# Simon-COVID.net
KiCad netlist of a schematic drawn in EAGLE
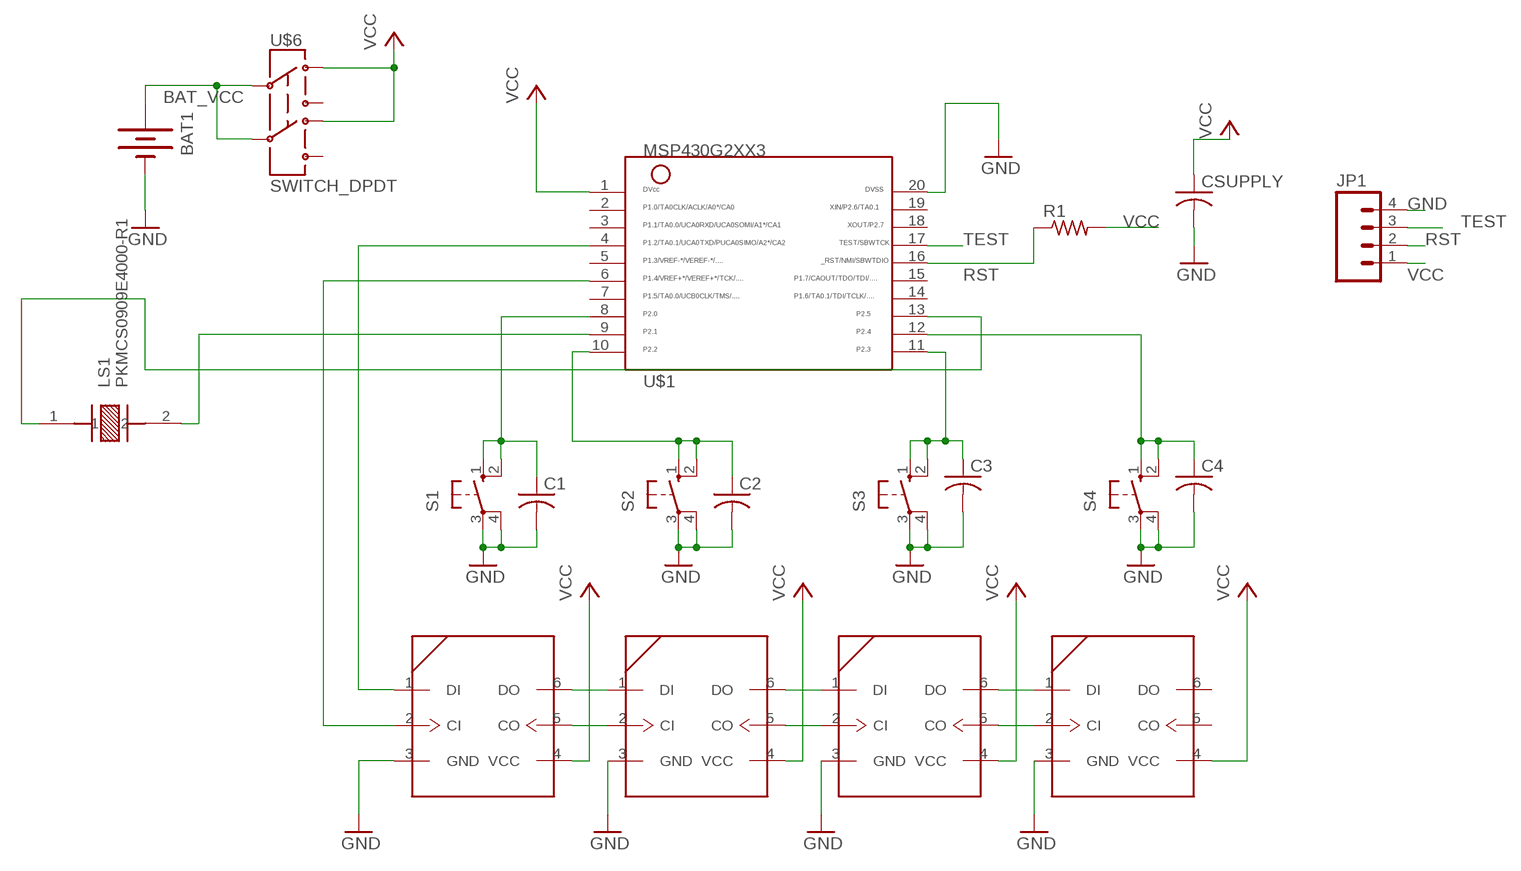
[diagram p0: schematic, sheet 1]

(export (version "E")
  (design (tool "Eeschema 10.0.6"))
  (components
    (comp (ref "BAT1")
      (value "BATTERY")
      (footprint "eagle-import:BATTERY_PACK_2AA")
      (libsource (lib "eagle-import") (part "BATTERY"))
    )
    (comp (ref "C1")
      (value "C-USC1206")
      (footprint "eagle-import:C1206")
      (libsource (lib "eagle-import") (part "C-USC1206"))
    )
    (comp (ref "C2")
      (value "C-USC1206")
      (footprint "eagle-import:C1206")
      (libsource (lib "eagle-import") (part "C-USC1206"))
    )
    (comp (ref "C3")
      (value "C-USC1206")
      (footprint "eagle-import:C1206")
      (libsource (lib "eagle-import") (part "C-USC1206"))
    )
    (comp (ref "C4")
      (value "C-USC1206")
      (footprint "eagle-import:C1206")
      (libsource (lib "eagle-import") (part "C-USC1206"))
    )
    (comp (ref "CSUPPLY")
      (value "C-USC1206")
      (footprint "eagle-import:C1206")
      (libsource (lib "eagle-import") (part "C-USC1206"))
    )
    (comp (ref "JP1")
      (value "M04LOCK")
      (footprint "eagle-import:1X04_LOCK")
      (libsource (lib "eagle-import") (part "M04LOCK"))
    )
    (comp (ref "LED1")
      (value "APA102")
      (footprint "eagle-import:5050")
      (libsource (lib "eagle-import") (part "APA102"))
    )
    (comp (ref "LED2")
      (value "APA102")
      (footprint "eagle-import:5050")
      (libsource (lib "eagle-import") (part "APA102"))
    )
    (comp (ref "LED3")
      (value "APA102")
      (footprint "eagle-import:5050")
      (libsource (lib "eagle-import") (part "APA102"))
    )
    (comp (ref "LED4")
      (value "APA102")
      (footprint "eagle-import:5050")
      (libsource (lib "eagle-import") (part "APA102"))
    )
    (comp (ref "LS1")
      (value "PKMCS0909E4000-R1")
      (footprint "eagle-import:XDCR_PKMCS0909E4000-R1")
      (fields (field (name "DIGI-KEY_PART_NUMBER") "490-9647-1-ND") (field (name "MF") "Murata"))
      (libsource (lib "eagle-import") (part "PKMCS0909E4000-R1"))
    )
    (comp (ref "R1")
      (value "R-US_R1206")
      (footprint "eagle-import:R1206")
      (libsource (lib "eagle-import") (part "R-US_R1206"))
    )
    (comp (ref "S1")
      (value "10-XX")
      (footprint "eagle-import:B3F-10XX")
      (fields (field (name "MPN") "B3F-1000"))
      (libsource (lib "eagle-import") (part "10-XX"))
    )
    (comp (ref "S2")
      (value "10-XX")
      (footprint "eagle-import:B3F-10XX")
      (fields (field (name "MPN") "B3F-1000"))
      (libsource (lib "eagle-import") (part "10-XX"))
    )
    (comp (ref "S3")
      (value "10-XX")
      (footprint "eagle-import:B3F-10XX")
      (fields (field (name "MPN") "B3F-1000"))
      (libsource (lib "eagle-import") (part "10-XX"))
    )
    (comp (ref "S4")
      (value "10-XX")
      (footprint "eagle-import:B3F-10XX")
      (fields (field (name "MPN") "B3F-1000"))
      (libsource (lib "eagle-import") (part "10-XX"))
    )
    (comp (ref "U$1")
      (value "MSP430G2XX3TSSOP")
      (footprint "eagle-import:PW20")
      (libsource (lib "eagle-import") (part "MSP430G2XX3TSSOP"))
    )
    (comp (ref "U$6")
      (value "SWITCH_DPDT")
      (footprint "eagle-import:JS_DPDT_TH")
      (libsource (lib "eagle-import") (part "SWITCH_DPDT"))
    )
  )
  (nets
    (net (code "1") (name "/BAT_VCC") (class "Default")
      (node (ref "BAT1") (pin "3V") (pinfunction "+_3V") (pintype "power_in"))
      (node (ref "U$6") (pin "2") (pinfunction "2_2") (pintype "bidirectional"))
      (node (ref "U$6") (pin "5") (pinfunction "5_5") (pintype "bidirectional"))
    )
    (net (code "2") (name "/RST") (class "Default")
      (node (ref "JP1") (pin "2") (pinfunction "2_2") (pintype "passive"))
      (node (ref "R1") (pin "1") (pinfunction "1_1") (pintype "passive"))
      (node (ref "U$1") (pin "16") (pinfunction "16_16") (pintype "bidirectional"))
    )
    (net (code "3") (name "/TEST") (class "Default")
      (node (ref "JP1") (pin "3") (pinfunction "3_3") (pintype "passive"))
      (node (ref "U$1") (pin "17") (pinfunction "17_17") (pintype "bidirectional"))
    )
    (net (code "4") (name "GND") (class "Default")
      (node (ref "BAT1") (pin "GND") (pinfunction "-_GND") (pintype "power_in"))
      (node (ref "C1") (pin "2") (pinfunction "2_2") (pintype "passive"))
      (node (ref "C2") (pin "2") (pinfunction "2_2") (pintype "passive"))
      (node (ref "C3") (pin "2") (pinfunction "2_2") (pintype "passive"))
      (node (ref "C4") (pin "2") (pinfunction "2_2") (pintype "passive"))
      (node (ref "CSUPPLY") (pin "2") (pinfunction "2_2") (pintype "passive"))
      (node (ref "JP1") (pin "4") (pinfunction "4_4") (pintype "passive"))
      (node (ref "LED1") (pin "3") (pinfunction "GND_3") (pintype "power_in"))
      (node (ref "LED2") (pin "3") (pinfunction "GND_3") (pintype "power_in"))
      (node (ref "LED3") (pin "3") (pinfunction "GND_3") (pintype "power_in"))
      (node (ref "LED4") (pin "3") (pinfunction "GND_3") (pintype "power_in"))
      (node (ref "S1") (pin "3") (pinfunction "P_3") (pintype "passive"))
      (node (ref "S1") (pin "4") (pinfunction "P1_4") (pintype "passive"))
      (node (ref "S2") (pin "3") (pinfunction "P_3") (pintype "passive"))
      (node (ref "S2") (pin "4") (pinfunction "P1_4") (pintype "passive"))
      (node (ref "S3") (pin "3") (pinfunction "P_3") (pintype "passive"))
      (node (ref "S3") (pin "4") (pinfunction "P1_4") (pintype "passive"))
      (node (ref "S4") (pin "3") (pinfunction "P_3") (pintype "passive"))
      (node (ref "S4") (pin "4") (pinfunction "P1_4") (pintype "passive"))
      (node (ref "U$1") (pin "20") (pinfunction "20_20") (pintype "bidirectional"))
    )
    (net (code "5") (name "Net-(LED1-CI)") (class "Default")
      (node (ref "LED1") (pin "2") (pinfunction "CI_2") (pintype "input"))
      (node (ref "U$1") (pin "6") (pinfunction "6_6") (pintype "bidirectional"))
    )
    (net (code "6") (name "Net-(LED1-CO)") (class "Default")
      (node (ref "LED1") (pin "5") (pinfunction "CO_5") (pintype "output"))
      (node (ref "LED2") (pin "2") (pinfunction "CI_2") (pintype "input"))
    )
    (net (code "7") (name "Net-(LED1-DI)") (class "Default")
      (node (ref "LED1") (pin "1") (pinfunction "DI_1") (pintype "input"))
      (node (ref "U$1") (pin "4") (pinfunction "4_4") (pintype "bidirectional"))
    )
    (net (code "8") (name "Net-(LED1-DO)") (class "Default")
      (node (ref "LED1") (pin "6") (pinfunction "DO_6") (pintype "output"))
      (node (ref "LED2") (pin "1") (pinfunction "DI_1") (pintype "input"))
    )
    (net (code "9") (name "Net-(LED2-CO)") (class "Default")
      (node (ref "LED2") (pin "5") (pinfunction "CO_5") (pintype "output"))
      (node (ref "LED3") (pin "2") (pinfunction "CI_2") (pintype "input"))
    )
    (net (code "10") (name "Net-(LED2-DO)") (class "Default")
      (node (ref "LED2") (pin "6") (pinfunction "DO_6") (pintype "output"))
      (node (ref "LED3") (pin "1") (pinfunction "DI_1") (pintype "input"))
    )
    (net (code "11") (name "Net-(LED3-CO)") (class "Default")
      (node (ref "LED3") (pin "5") (pinfunction "CO_5") (pintype "output"))
      (node (ref "LED4") (pin "2") (pinfunction "CI_2") (pintype "input"))
    )
    (net (code "12") (name "Net-(LED3-DO)") (class "Default")
      (node (ref "LED3") (pin "6") (pinfunction "DO_6") (pintype "output"))
      (node (ref "LED4") (pin "1") (pinfunction "DI_1") (pintype "input"))
    )
    (net (code "13") (name "Net-(LS1-Pad1)") (class "Default")
      (node (ref "LS1") (pin "1") (pinfunction "1_1") (pintype "passive"))
      (node (ref "U$1") (pin "13") (pinfunction "13_13") (pintype "bidirectional"))
    )
    (net (code "14") (name "Net-(LS1-Pad2)") (class "Default")
      (node (ref "LS1") (pin "2") (pinfunction "2_2") (pintype "passive"))
      (node (ref "U$1") (pin "9") (pinfunction "9_9") (pintype "bidirectional"))
    )
    (net (code "15") (name "Net-(S1-S)") (class "Default")
      (node (ref "C1") (pin "1") (pinfunction "1_1") (pintype "passive"))
      (node (ref "S1") (pin "1") (pinfunction "S_1") (pintype "passive"))
      (node (ref "S1") (pin "2") (pinfunction "S1_2") (pintype "passive"))
      (node (ref "U$1") (pin "8") (pinfunction "8_8") (pintype "bidirectional"))
    )
    (net (code "16") (name "Net-(S2-S)") (class "Default")
      (node (ref "C2") (pin "1") (pinfunction "1_1") (pintype "passive"))
      (node (ref "S2") (pin "1") (pinfunction "S_1") (pintype "passive"))
      (node (ref "S2") (pin "2") (pinfunction "S1_2") (pintype "passive"))
      (node (ref "U$1") (pin "10") (pinfunction "10_10") (pintype "bidirectional"))
    )
    (net (code "17") (name "Net-(S3-S)") (class "Default")
      (node (ref "C3") (pin "1") (pinfunction "1_1") (pintype "passive"))
      (node (ref "S3") (pin "1") (pinfunction "S_1") (pintype "passive"))
      (node (ref "S3") (pin "2") (pinfunction "S1_2") (pintype "passive"))
      (node (ref "U$1") (pin "11") (pinfunction "11_11") (pintype "bidirectional"))
    )
    (net (code "18") (name "Net-(S4-S)") (class "Default")
      (node (ref "C4") (pin "1") (pinfunction "1_1") (pintype "passive"))
      (node (ref "S4") (pin "1") (pinfunction "S_1") (pintype "passive"))
      (node (ref "S4") (pin "2") (pinfunction "S1_2") (pintype "passive"))
      (node (ref "U$1") (pin "12") (pinfunction "12_12") (pintype "bidirectional"))
    )
    (net (code "19") (name "VCC") (class "Default")
      (node (ref "CSUPPLY") (pin "1") (pinfunction "1_1") (pintype "passive"))
      (node (ref "JP1") (pin "1") (pinfunction "1_1") (pintype "passive"))
      (node (ref "LED1") (pin "4") (pinfunction "VCC_4") (pintype "power_in"))
      (node (ref "LED2") (pin "4") (pinfunction "VCC_4") (pintype "power_in"))
      (node (ref "LED3") (pin "4") (pinfunction "VCC_4") (pintype "power_in"))
      (node (ref "LED4") (pin "4") (pinfunction "VCC_4") (pintype "power_in"))
      (node (ref "R1") (pin "2") (pinfunction "2_2") (pintype "passive"))
      (node (ref "U$1") (pin "1") (pinfunction "1_1") (pintype "bidirectional"))
      (node (ref "U$6") (pin "1") (pinfunction "1_1") (pintype "bidirectional"))
      (node (ref "U$6") (pin "4") (pinfunction "4_4") (pintype "bidirectional"))
    )
    (net (code "20") (name "unconnected-(LED4-CO-Pad5)") (class "Default")
      (node (ref "LED4") (pin "5") (pinfunction "CO_5") (pintype "output"))
    )
    (net (code "21") (name "unconnected-(LED4-DO-Pad6)") (class "Default")
      (node (ref "LED4") (pin "6") (pinfunction "DO_6") (pintype "output"))
    )
    (net (code "22") (name "unconnected-(U$1-Pad2)") (class "Default")
      (node (ref "U$1") (pin "2") (pinfunction "2_2") (pintype "bidirectional"))
    )
    (net (code "23") (name "unconnected-(U$1-Pad3)") (class "Default")
      (node (ref "U$1") (pin "3") (pinfunction "3_3") (pintype "bidirectional"))
    )
    (net (code "24") (name "unconnected-(U$1-Pad5)") (class "Default")
      (node (ref "U$1") (pin "5") (pinfunction "5_5") (pintype "bidirectional"))
    )
    (net (code "25") (name "unconnected-(U$1-Pad7)") (class "Default")
      (node (ref "U$1") (pin "7") (pinfunction "7_7") (pintype "bidirectional"))
    )
    (net (code "26") (name "unconnected-(U$1-Pad14)") (class "Default")
      (node (ref "U$1") (pin "14") (pinfunction "14_14") (pintype "bidirectional"))
    )
    (net (code "27") (name "unconnected-(U$1-Pad15)") (class "Default")
      (node (ref "U$1") (pin "15") (pinfunction "15_15") (pintype "bidirectional"))
    )
    (net (code "28") (name "unconnected-(U$1-Pad18)") (class "Default")
      (node (ref "U$1") (pin "18") (pinfunction "18_18") (pintype "bidirectional"))
    )
    (net (code "29") (name "unconnected-(U$1-Pad19)") (class "Default")
      (node (ref "U$1") (pin "19") (pinfunction "19_19") (pintype "bidirectional"))
    )
    (net (code "30") (name "unconnected-(U$6-Pad3)") (class "Default")
      (node (ref "U$6") (pin "3") (pinfunction "3_3") (pintype "bidirectional"))
    )
    (net (code "31") (name "unconnected-(U$6-Pad6)") (class "Default")
      (node (ref "U$6") (pin "6") (pinfunction "6_6") (pintype "bidirectional"))
    )
  )
)
